# OV2640.net
KiCad netlist of a schematic drawn in EAGLE
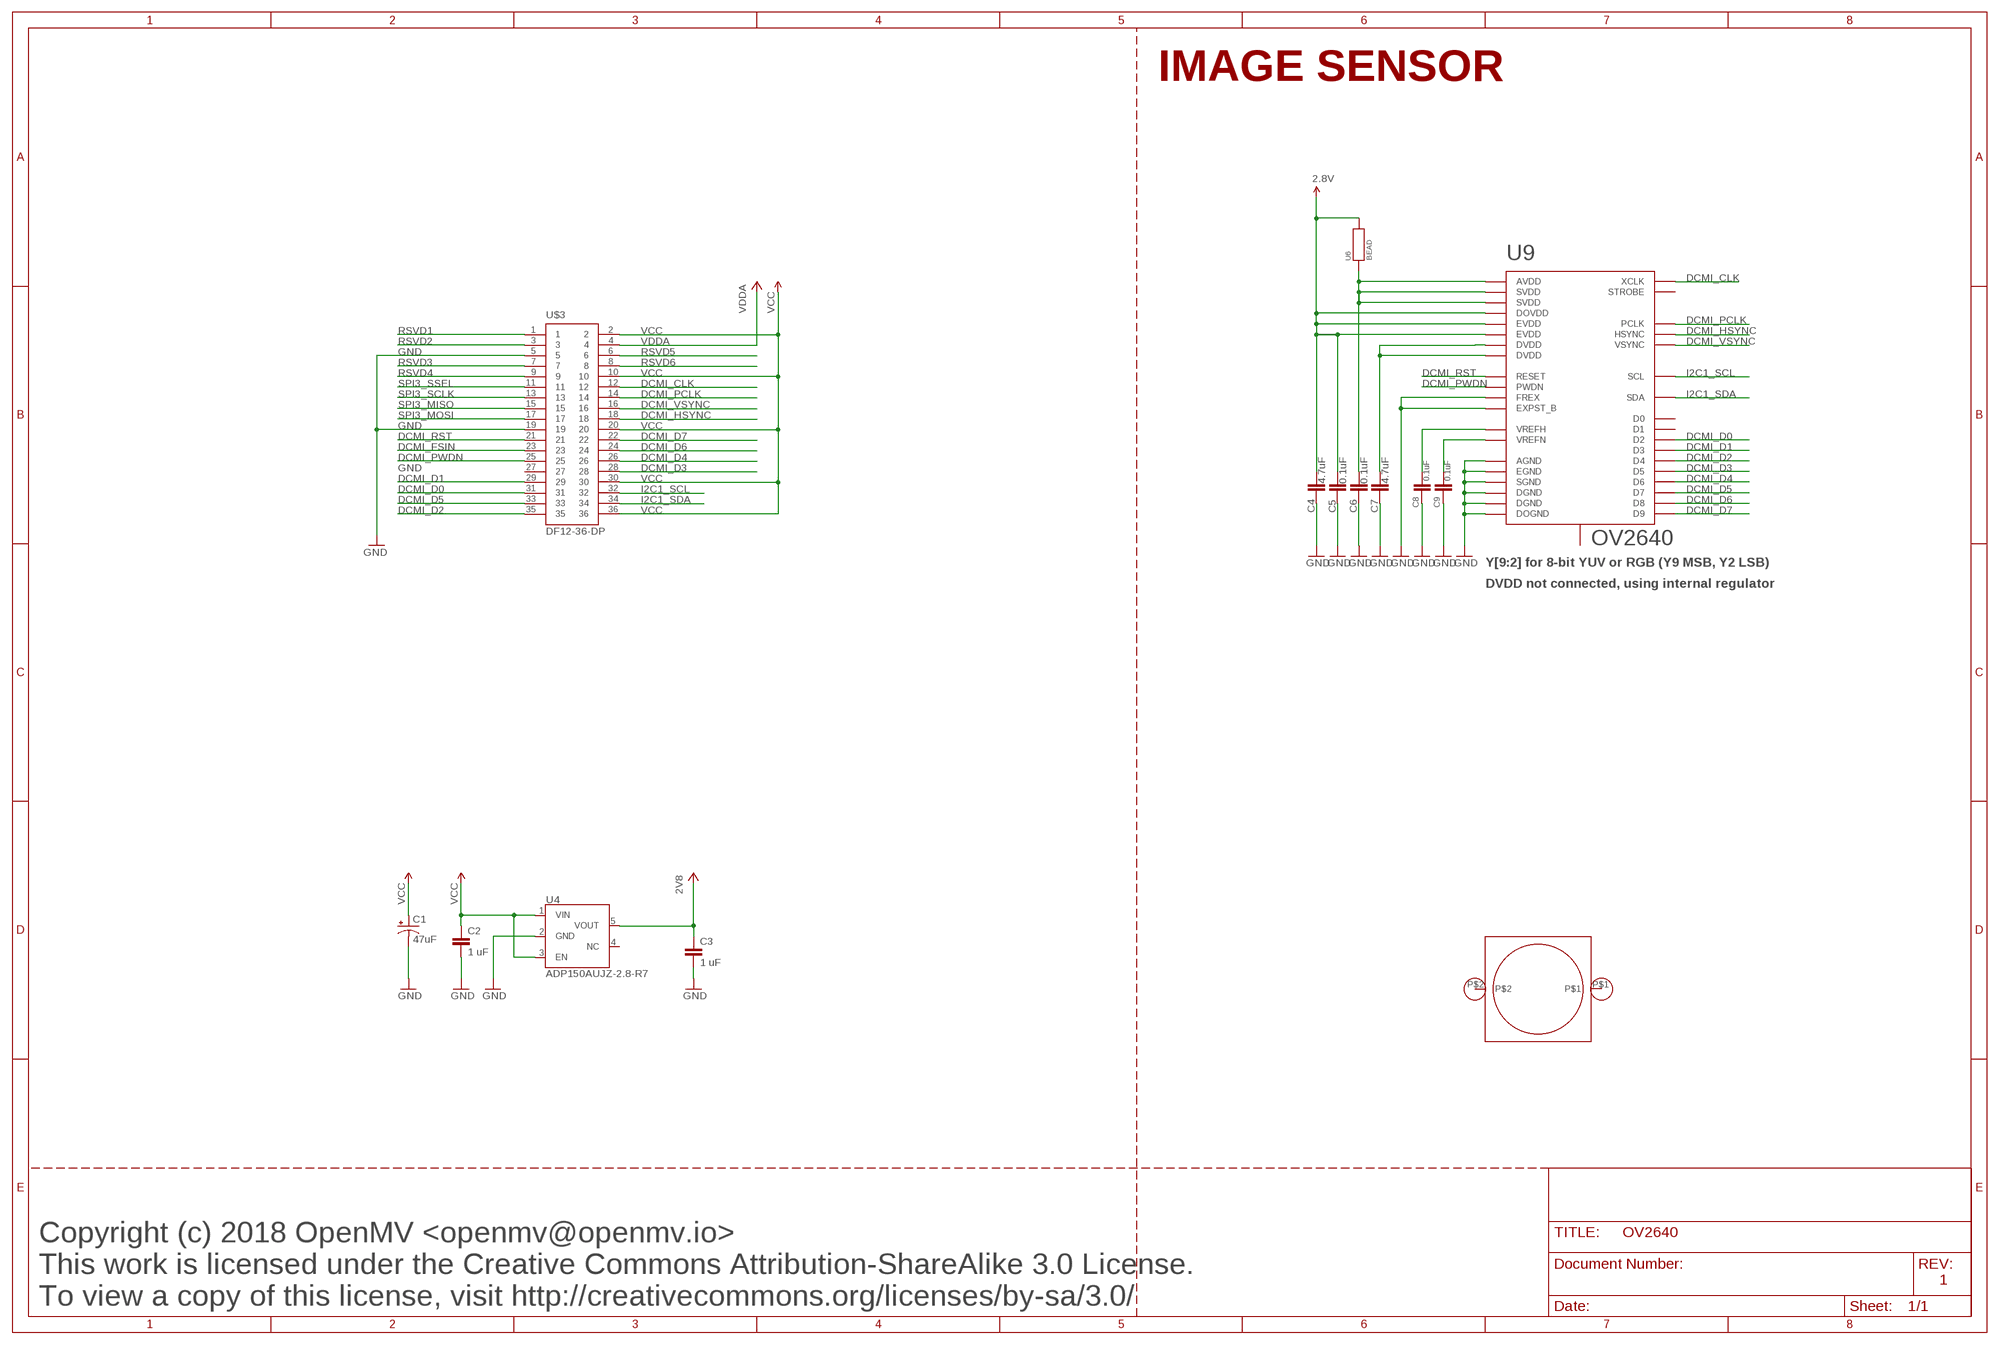
[diagram p0: schematic, sheet 1]

(export (version "E")
  (design (tool "Eeschema 10.0.6"))
  (components
    (comp (ref "C1")
      (value "47uF")
      (footprint "eagle-import:EIA3216")
      (libsource (lib "eagle-import") (part "CAP_POL1206"))
    )
    (comp (ref "C2")
      (value "1 uF")
      (footprint "eagle-import:0402-CAP")
      (libsource (lib "eagle-import") (part "CAP0402-CAP"))
    )
    (comp (ref "C3")
      (value "1 uF")
      (footprint "eagle-import:0402-CAP")
      (libsource (lib "eagle-import") (part "CAP0402-CAP"))
    )
    (comp (ref "C4")
      (value "4.7uF")
      (footprint "eagle-import:0402-CAP")
      (libsource (lib "eagle-import") (part "sfe_CAP0402-CAP"))
    )
    (comp (ref "C5")
      (value "0.1uF")
      (footprint "eagle-import:0402-CAP")
      (libsource (lib "eagle-import") (part "sfe_CAP0402-CAP"))
    )
    (comp (ref "C6")
      (value "0.1uF")
      (footprint "eagle-import:0402-CAP")
      (libsource (lib "eagle-import") (part "sfe_CAP0402-CAP"))
    )
    (comp (ref "C7")
      (value "4.7uF")
      (footprint "eagle-import:0402-CAP")
      (libsource (lib "eagle-import") (part "sfe_CAP0402-CAP"))
    )
    (comp (ref "C8")
      (value "0.1uF")
      (footprint "eagle-import:0402-CAP")
      (libsource (lib "eagle-import") (part "sfe_CAP0402-CAP"))
    )
    (comp (ref "C9")
      (value "0.1uF")
      (footprint "eagle-import:0402-CAP")
      (libsource (lib "eagle-import") (part "sfe_CAP0402-CAP"))
    )
    (comp (ref "LM1")
      (value "LENSMOUNT20MM")
      (footprint "eagle-import:LENSMOUNT-20MM")
      (libsource (lib "eagle-import") (part "LENSMOUNT20MM"))
    )
    (comp (ref "U$3")
      (value "DF12-36-DP")
      (footprint "eagle-import:DF12-36-DP")
      (libsource (lib "eagle-import") (part "DF12-36-DP"))
    )
    (comp (ref "U4")
      (value "ADP150AUJZ-2.8-R7")
      (footprint "eagle-import:SOT23-5")
      (libsource (lib "eagle-import") (part "ADP150TSOT-5"))
    )
    (comp (ref "U6")
      (value "BEAD")
      (footprint "eagle-import:0402-CAP")
      (libsource (lib "eagle-import") (part "BEAD"))
    )
    (comp (ref "U9")
      (value "OV2640")
      (footprint "eagle-import:CSP2")
      (libsource (lib "eagle-import") (part "OV2640"))
    )
  )
  (nets
    (net (code "1") (name "/DCMI_CLK") (class "Default")
      (node (ref "U$3") (pin "12") (pinfunction "12_12") (pintype "bidirectional"))
      (node (ref "U9") (pin "C4") (pinfunction "XCLK_C4") (pintype "bidirectional"))
    )
    (net (code "2") (name "/DCMI_D0") (class "Default")
      (node (ref "U$3") (pin "31") (pinfunction "31_31") (pintype "bidirectional"))
      (node (ref "U9") (pin "F3") (pinfunction "D2_F3") (pintype "bidirectional"))
    )
    (net (code "3") (name "/DCMI_D1") (class "Default")
      (node (ref "U$3") (pin "29") (pinfunction "29_29") (pintype "bidirectional"))
      (node (ref "U9") (pin "G3") (pinfunction "D3_G3") (pintype "bidirectional"))
    )
    (net (code "4") (name "/DCMI_D2") (class "Default")
      (node (ref "U$3") (pin "35") (pinfunction "35_35") (pintype "bidirectional"))
      (node (ref "U9") (pin "F4") (pinfunction "D4_F4") (pintype "bidirectional"))
    )
    (net (code "5") (name "/DCMI_D3") (class "Default")
      (node (ref "U$3") (pin "28") (pinfunction "28_28") (pintype "bidirectional"))
      (node (ref "U9") (pin "G4") (pinfunction "D5_G4") (pintype "bidirectional"))
    )
    (net (code "6") (name "/DCMI_D4") (class "Default")
      (node (ref "U$3") (pin "26") (pinfunction "26_26") (pintype "bidirectional"))
      (node (ref "U9") (pin "E5") (pinfunction "D6_E5") (pintype "bidirectional"))
    )
    (net (code "7") (name "/DCMI_D5") (class "Default")
      (node (ref "U$3") (pin "33") (pinfunction "33_33") (pintype "bidirectional"))
      (node (ref "U9") (pin "G5") (pinfunction "D7_G5") (pintype "bidirectional"))
    )
    (net (code "8") (name "/DCMI_D6") (class "Default")
      (node (ref "U$3") (pin "24") (pinfunction "24_24") (pintype "bidirectional"))
      (node (ref "U9") (pin "F5") (pinfunction "D8_F5") (pintype "bidirectional"))
    )
    (net (code "9") (name "/DCMI_D7") (class "Default")
      (node (ref "U$3") (pin "22") (pinfunction "22_22") (pintype "bidirectional"))
      (node (ref "U9") (pin "G6") (pinfunction "D9_G6") (pintype "bidirectional"))
    )
    (net (code "10") (name "/DCMI_FSIN") (class "Default")
      (node (ref "U$3") (pin "23") (pinfunction "23_23") (pintype "bidirectional"))
    )
    (net (code "11") (name "/DCMI_HSYNC") (class "Default")
      (node (ref "U$3") (pin "18") (pinfunction "18_18") (pintype "bidirectional"))
      (node (ref "U9") (pin "C3") (pinfunction "HSYNC_C3") (pintype "bidirectional"))
    )
    (net (code "12") (name "/DCMI_PCLK") (class "Default")
      (node (ref "U$3") (pin "14") (pinfunction "14_14") (pintype "bidirectional"))
      (node (ref "U9") (pin "E3") (pinfunction "PCLK_E3") (pintype "bidirectional"))
    )
    (net (code "13") (name "/DCMI_PWDN") (class "Default")
      (node (ref "U$3") (pin "25") (pinfunction "25_25") (pintype "bidirectional"))
      (node (ref "U9") (pin "B6") (pinfunction "PWDN_B6") (pintype "bidirectional"))
    )
    (net (code "14") (name "/DCMI_RST") (class "Default")
      (node (ref "U$3") (pin "21") (pinfunction "21_21") (pintype "bidirectional"))
      (node (ref "U9") (pin "C6") (pinfunction "RESET_C6") (pintype "bidirectional"))
    )
    (net (code "15") (name "/DCMI_VSYNC") (class "Default")
      (node (ref "U$3") (pin "16") (pinfunction "16_16") (pintype "bidirectional"))
      (node (ref "U9") (pin "D2") (pinfunction "VSYNC_D2") (pintype "bidirectional"))
    )
    (net (code "16") (name "/I2C1_SCL") (class "Default")
      (node (ref "U$3") (pin "32") (pinfunction "32_32") (pintype "bidirectional"))
      (node (ref "U9") (pin "C2") (pinfunction "SCL_C2") (pintype "bidirectional"))
    )
    (net (code "17") (name "/I2C1_SDA") (class "Default")
      (node (ref "U$3") (pin "34") (pinfunction "34_34") (pintype "bidirectional"))
      (node (ref "U9") (pin "C1") (pinfunction "SDA_C1") (pintype "bidirectional"))
    )
    (net (code "18") (name "/P$1") (class "Default")
      (node (ref "LM1") (pin "P$1") (pinfunction "P$1_P$1") (pintype "power_in"))
    )
    (net (code "19") (name "/P$2") (class "Default")
      (node (ref "LM1") (pin "P$2") (pinfunction "P$2_P$2") (pintype "power_in"))
    )
    (net (code "20") (name "/RSVD1") (class "Default")
      (node (ref "U$3") (pin "1") (pinfunction "1_1") (pintype "bidirectional"))
    )
    (net (code "21") (name "/RSVD2") (class "Default")
      (node (ref "U$3") (pin "3") (pinfunction "3_3") (pintype "bidirectional"))
    )
    (net (code "22") (name "/RSVD3") (class "Default")
      (node (ref "U$3") (pin "7") (pinfunction "7_7") (pintype "bidirectional"))
    )
    (net (code "23") (name "/RSVD4") (class "Default")
      (node (ref "U$3") (pin "9") (pinfunction "9_9") (pintype "bidirectional"))
    )
    (net (code "24") (name "/RSVD5") (class "Default")
      (node (ref "U$3") (pin "6") (pinfunction "6_6") (pintype "bidirectional"))
    )
    (net (code "25") (name "/RSVD6") (class "Default")
      (node (ref "U$3") (pin "8") (pinfunction "8_8") (pintype "bidirectional"))
    )
    (net (code "26") (name "/SPI3_MISO") (class "Default")
      (node (ref "U$3") (pin "15") (pinfunction "15_15") (pintype "bidirectional"))
    )
    (net (code "27") (name "/SPI3_MOSI") (class "Default")
      (node (ref "U$3") (pin "17") (pinfunction "17_17") (pintype "bidirectional"))
    )
    (net (code "28") (name "/SPI3_SCLK") (class "Default")
      (node (ref "U$3") (pin "13") (pinfunction "13_13") (pintype "bidirectional"))
    )
    (net (code "29") (name "/SPI3_SSEL") (class "Default")
      (node (ref "U$3") (pin "11") (pinfunction "11_11") (pintype "bidirectional"))
    )
    (net (code "30") (name "2.8V") (class "Default")
      (node (ref "C4") (pin "1") (pinfunction "1_1") (pintype "passive"))
      (node (ref "C5") (pin "1") (pinfunction "1_1") (pintype "passive"))
      (node (ref "U6") (pin "2") (pinfunction "2_2") (pintype "passive"))
      (node (ref "U9") (pin "B1") (pinfunction "DOVDD_B1") (pintype "power_in"))
      (node (ref "U9") (pin "F1") (pinfunction "EVDD_F1") (pintype "power_in"))
      (node (ref "U9") (pin "G1") (pinfunction "EVDD_G1") (pintype "power_in"))
    )
    (net (code "31") (name "2V8") (class "Default")
      (node (ref "C3") (pin "1") (pinfunction "1_1") (pintype "passive"))
      (node (ref "U4") (pin "5") (pinfunction "VOUT_5") (pintype "power_in"))
    )
    (net (code "32") (name "GND") (class "Default")
      (node (ref "C1") (pin "C") (pinfunction "-_C") (pintype "passive"))
      (node (ref "C2") (pin "2") (pinfunction "2_2") (pintype "passive"))
      (node (ref "C3") (pin "2") (pinfunction "2_2") (pintype "passive"))
      (node (ref "C4") (pin "2") (pinfunction "2_2") (pintype "passive"))
      (node (ref "C5") (pin "2") (pinfunction "2_2") (pintype "passive"))
      (node (ref "C6") (pin "2") (pinfunction "2_2") (pintype "passive"))
      (node (ref "C7") (pin "2") (pinfunction "2_2") (pintype "passive"))
      (node (ref "C8") (pin "2") (pinfunction "2_2") (pintype "passive"))
      (node (ref "C9") (pin "2") (pinfunction "2_2") (pintype "passive"))
      (node (ref "U$3") (pin "19") (pinfunction "19_19") (pintype "bidirectional"))
      (node (ref "U$3") (pin "5") (pinfunction "5_5") (pintype "bidirectional"))
      (node (ref "U4") (pin "2") (pinfunction "GND_2") (pintype "power_in"))
      (node (ref "U9") (pin "A1") (pinfunction "DOGND_A1") (pintype "power_in"))
      (node (ref "U9") (pin "A2") (pinfunction "EXPST_B_A2") (pintype "output"))
      (node (ref "U9") (pin "A3") (pinfunction "AGND_A3") (pintype "power_in"))
      (node (ref "U9") (pin "A4") (pinfunction "SGND_A4") (pintype "power_in"))
      (node (ref "U9") (pin "B2") (pinfunction "FREX_B2") (pintype "input"))
      (node (ref "U9") (pin "E4") (pinfunction "EGND_E4") (pintype "power_in"))
      (node (ref "U9") (pin "E6") (pinfunction "DGND_E6") (pintype "power_in"))
      (node (ref "U9") (pin "G2") (pinfunction "DGND_G2") (pintype "power_in"))
    )
    (net (code "33") (name "Net-(C7-Pad1)") (class "Default")
      (node (ref "C7") (pin "1") (pinfunction "1_1") (pintype "passive"))
      (node (ref "U9") (pin "F2") (pinfunction "DVDD_F2") (pintype "power_in"))
      (node (ref "U9") (pin "F6") (pinfunction "DVDD_F6") (pintype "power_in"))
    )
    (net (code "34") (name "Net-(U9-AVDD)") (class "Default")
      (node (ref "C6") (pin "1") (pinfunction "1_1") (pintype "passive"))
      (node (ref "U6") (pin "1") (pinfunction "1_1") (pintype "passive"))
      (node (ref "U9") (pin "B3") (pinfunction "AVDD_B3") (pintype "power_in"))
      (node (ref "U9") (pin "B4") (pinfunction "SVDD_B4") (pintype "power_in"))
      (node (ref "U9") (pin "B5") (pinfunction "SVDD_B5") (pintype "power_in"))
    )
    (net (code "35") (name "Net-(U9-VREFH)") (class "Default")
      (node (ref "C8") (pin "1") (pinfunction "1_1") (pintype "passive"))
      (node (ref "U9") (pin "C5") (pinfunction "VREFH_C5") (pintype "power_in"))
    )
    (net (code "36") (name "Net-(U9-VREFN)") (class "Default")
      (node (ref "C9") (pin "1") (pinfunction "1_1") (pintype "passive"))
      (node (ref "U9") (pin "A5") (pinfunction "VREFN_A5") (pintype "power_in"))
    )
    (net (code "37") (name "VCC") (class "Default")
      (node (ref "C1") (pin "A") (pinfunction "+_A") (pintype "passive"))
      (node (ref "C2") (pin "1") (pinfunction "1_1") (pintype "passive"))
      (node (ref "U$3") (pin "10") (pinfunction "10_10") (pintype "bidirectional"))
      (node (ref "U$3") (pin "2") (pinfunction "2_2") (pintype "bidirectional"))
      (node (ref "U$3") (pin "20") (pinfunction "20_20") (pintype "bidirectional"))
      (node (ref "U$3") (pin "30") (pinfunction "30_30") (pintype "bidirectional"))
      (node (ref "U$3") (pin "36") (pinfunction "36_36") (pintype "bidirectional"))
      (node (ref "U4") (pin "1") (pinfunction "VIN_1") (pintype "power_in"))
      (node (ref "U4") (pin "3") (pinfunction "EN_3") (pintype "bidirectional"))
    )
    (net (code "38") (name "VDDA") (class "Default")
      (node (ref "U$3") (pin "4") (pinfunction "4_4") (pintype "bidirectional"))
    )
    (net (code "39") (name "unconnected-(U$3-Pad27)") (class "Default")
      (node (ref "U$3") (pin "27") (pinfunction "27_27") (pintype "bidirectional"))
    )
    (net (code "40") (name "unconnected-(U4-NC-Pad4)") (class "Default")
      (node (ref "U4") (pin "4") (pinfunction "NC_4") (pintype "bidirectional"))
    )
    (net (code "41") (name "unconnected-(U9-D0-PadE2)") (class "Default")
      (node (ref "U9") (pin "E2") (pinfunction "D0_E2") (pintype "bidirectional"))
    )
    (net (code "42") (name "unconnected-(U9-D1-PadE1)") (class "Default")
      (node (ref "U9") (pin "E1") (pinfunction "D1_E1") (pintype "bidirectional"))
    )
    (net (code "43") (name "unconnected-(U9-NC-PadD6)") (class "Default")
      (node (ref "U9") (pin "D6") (pinfunction "NC_D6") (pintype "no_connect"))
    )
    (net (code "44") (name "unconnected-(U9-STROBE-PadA6)") (class "Default")
      (node (ref "U9") (pin "A6") (pinfunction "STROBE_A6") (pintype "output"))
    )
  )
)
